# Sheet5.net
KiCad netlist of a schematic drawn in Altium Designer
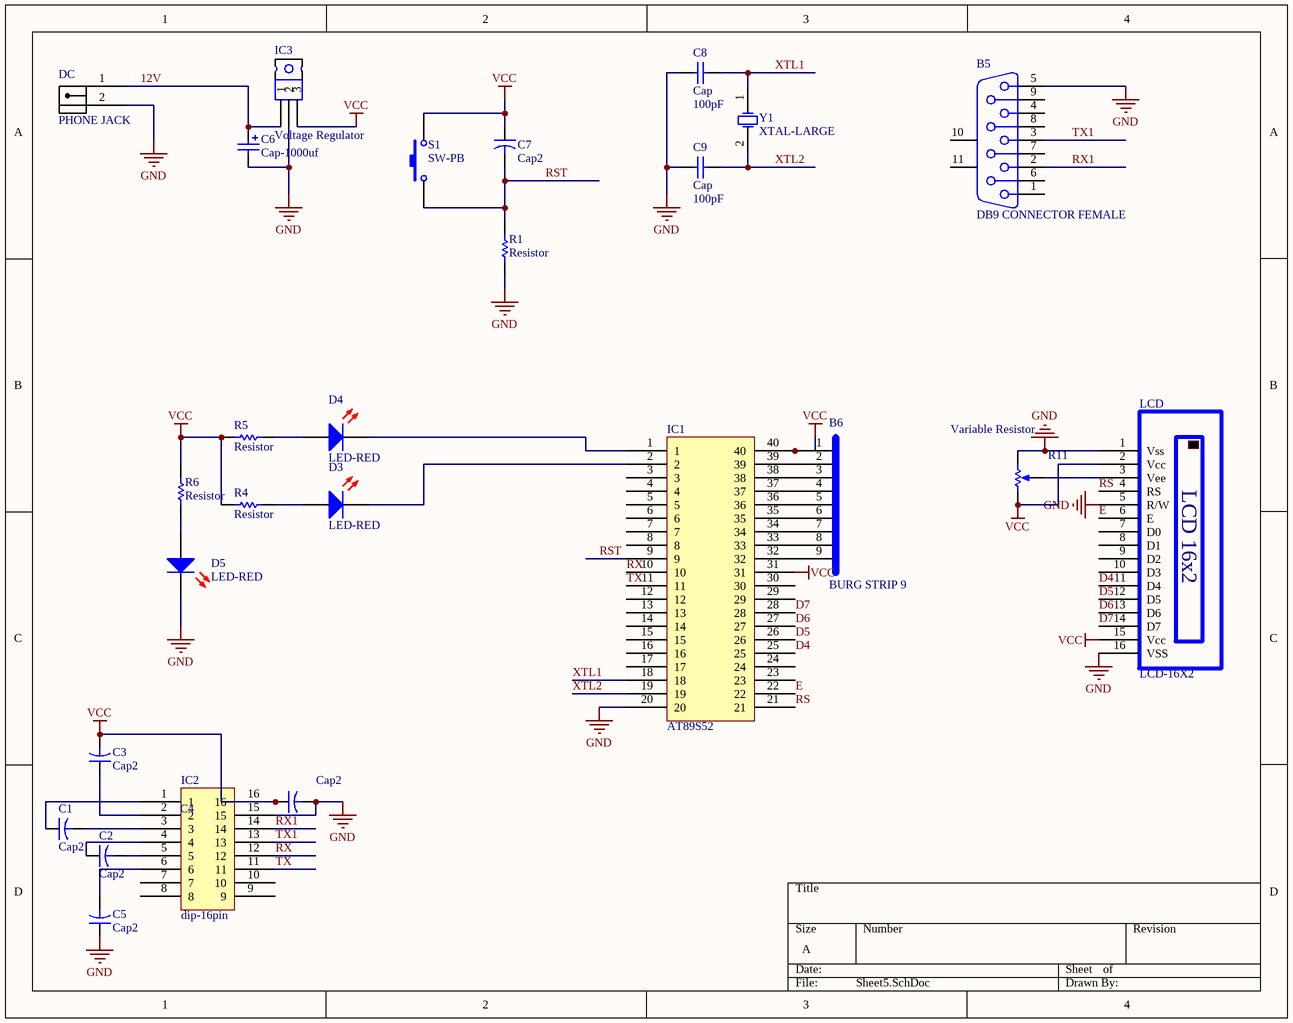
[diagram p0: Sheet5.SchDoc]

(export (version "E")
  (design (tool "Eeschema 10.0.6"))
  (components
    (comp (ref "B5")
      (value "DB9 CONNECTOR FEMALE")
      (footprint "DB9 CONNECTOR FEMALE")
      (libsource (lib "Devindia_v4.0") (part "DB9 CONNECTOR FEMALE"))
    )
    (comp (ref "B6")
      (value "BURG STRIP 9")
      (footprint "bergstrip-9pin")
      (libsource (lib "Devindia_v4.0") (part "BURG STRIP 9"))
    )
    (comp (ref "C1") (value "Cap2") (footprint "CAP-100uf") (libsource (lib "Devindia_v4.0") (part "Cap2")))
    (comp (ref "C2") (value "Cap2") (footprint "CAP-100uf") (libsource (lib "Devindia_v4.0") (part "Cap2")))
    (comp (ref "C3") (value "Cap2") (footprint "CAP-100uf") (libsource (lib "Devindia_v4.0") (part "Cap2")))
    (comp (ref "C4") (value "Cap2") (footprint "CAP-100uf") (libsource (lib "Devindia_v4.0") (part "Cap2")))
    (comp (ref "C5") (value "Cap2") (footprint "CAP-100uf") (libsource (lib "Devindia_v4.0") (part "Cap2")))
    (comp (ref "C6")
      (value "Cap-1000uf")
      (footprint "CAP-1000uf")
      (libsource (lib "Devindia_v4.0") (part "Cap-1000uf"))
    )
    (comp (ref "C7") (value "Cap2") (footprint "CAP-100uf") (libsource (lib "Devindia_v4.0") (part "Cap2")))
    (comp (ref "C8")
      (value "Cap")
      (footprint "CAP")
      (description "Capacitor")
      (fields (field (name "ALTIUM_VALUE") "100pF") (field (name "PUBLISHER") "Altium Limited"))
      (libsource (lib "Devindia_v4.0") (part "Cap"))
    )
    (comp (ref "C9")
      (value "Cap")
      (footprint "CAP")
      (description "Capacitor")
      (fields (field (name "ALTIUM_VALUE") "100pF") (field (name "PUBLISHER") "Altium Limited"))
      (libsource (lib "Devindia_v4.0") (part "Cap"))
    )
    (comp (ref "D3")
      (value "LED-RED")
      (footprint "LED-RED")
      (description "Typical BLUE SiC LED")
      (fields (field (name "PUBLISHER") "Altium Limited"))
      (libsource (lib "Devindia_v4.0") (part "LED-RED"))
    )
    (comp (ref "D4")
      (value "LED-RED")
      (footprint "LED-RED")
      (description "Typical BLUE SiC LED")
      (fields (field (name "PUBLISHER") "Altium Limited"))
      (libsource (lib "Devindia_v4.0") (part "LED-RED"))
    )
    (comp (ref "D5")
      (value "LED-RED")
      (footprint "LED-RED")
      (description "Typical BLUE SiC LED")
      (fields (field (name "PUBLISHER") "Altium Limited"))
      (libsource (lib "Devindia_v4.0") (part "LED-RED"))
    )
    (comp (ref "DC")
      (value "PHONE JACK")
      (footprint "PHONE JACK")
      (libsource (lib "Devindia_v4.0") (part "PHONE JACK"))
    )
    (comp (ref "IC1")
      (value "AT89S52")
      (footprint "AT89S52")
      (libsource (lib "Devindia_v4.0") (part "AT89S52"))
    )
    (comp (ref "IC2")
      (value "dip-16pin")
      (footprint "dip-16pin")
      (libsource (lib "Devindia_v4.0") (part "dip-16pin"))
    )
    (comp (ref "IC3")
      (value "Voltage Regulator")
      (footprint "7805 WITH HEAT-SINK")
      (libsource (lib "Devindia_v4.0") (part "7805 HEATSINK"))
    )
    (comp (ref "LCD")
      (value "LCD-16X2")
      (footprint "LCD-16x2")
      (libsource (lib "Devindia_v4.0") (part "LCD-16X2"))
    )
    (comp (ref "R1")
      (value "Resistor")
      (footprint "res-2.54x4")
      (libsource (lib "Devindia_v4.0") (part "Resistor 2.54x4"))
    )
    (comp (ref "R4")
      (value "Resistor")
      (footprint "res-2.54x4")
      (libsource (lib "Devindia_v4.0") (part "Resistor 2.54x4"))
    )
    (comp (ref "R5")
      (value "Resistor")
      (footprint "res-2.54x4")
      (libsource (lib "Devindia_v4.0") (part "Resistor 2.54x4"))
    )
    (comp (ref "R6")
      (value "Resistor")
      (footprint "res-2.54x4")
      (libsource (lib "Devindia_v4.0") (part "Resistor 2.54x4"))
    )
    (comp (ref "R11")
      (value "Variable Resistor")
      (footprint "reg-variable")
      (libsource (lib "Devindia_v4.0") (part "Variable Resistor"))
    )
    (comp (ref "S1")
      (value "SW-PB")
      (footprint "sw-pb")
      (description "Switch")
      (fields (field (name "PUBLISHER") "Altium Limited"))
      (libsource (lib "Devindia_v4.0") (part "SW-PB"))
    )
    (comp (ref "Y1")
      (value "XTAL-LARGE")
      (footprint "XTAL-LARGE")
      (description "Crystal Oscillator")
      (fields (field (name "PUBLISHER") "Altium Limited"))
      (libsource (lib "Devindia_v4.0") (part "XTAL-LARGE"))
    )
  )
  (nets
    (net (code "1") (name "/12V") (class "Default")
      (node (ref "C6") (pin "1") (pinfunction "1_1") (pintype "passive"))
      (node (ref "DC") (pin "1") (pinfunction "1_1") (pintype "passive"))
      (node (ref "IC3") (pin "1") (pinfunction "1_1") (pintype "passive"))
    )
    (net (code "2") (name "/D4") (class "Default")
      (node (ref "IC1") (pin "25") (pinfunction "25_25") (pintype "passive"))
      (node (ref "LCD") (pin "11") (pinfunction "D4_11") (pintype "passive"))
    )
    (net (code "3") (name "/D5") (class "Default")
      (node (ref "IC1") (pin "26") (pinfunction "26_26") (pintype "passive"))
      (node (ref "LCD") (pin "12") (pinfunction "D5_12") (pintype "passive"))
    )
    (net (code "4") (name "/D6") (class "Default")
      (node (ref "IC1") (pin "27") (pinfunction "27_27") (pintype "passive"))
      (node (ref "LCD") (pin "13") (pinfunction "D6_13") (pintype "passive"))
    )
    (net (code "5") (name "/D7") (class "Default")
      (node (ref "IC1") (pin "28") (pinfunction "28_28") (pintype "passive"))
      (node (ref "LCD") (pin "14") (pinfunction "D7_14") (pintype "passive"))
    )
    (net (code "6") (name "/E") (class "Default")
      (node (ref "IC1") (pin "22") (pinfunction "22_22") (pintype "passive"))
      (node (ref "LCD") (pin "6") (pinfunction "E_6") (pintype "passive"))
    )
    (net (code "7") (name "/RS") (class "Default")
      (node (ref "IC1") (pin "21") (pinfunction "21_21") (pintype "passive"))
      (node (ref "LCD") (pin "4") (pinfunction "RS_4") (pintype "passive"))
    )
    (net (code "8") (name "/RST") (class "Default")
      (node (ref "C7") (pin "2") (pinfunction "2_2") (pintype "passive"))
      (node (ref "IC1") (pin "9") (pinfunction "9_9") (pintype "passive"))
      (node (ref "R1") (pin "2") (pinfunction "2_2") (pintype "passive"))
      (node (ref "S1") (pin "1") (pinfunction "1_1") (pintype "passive"))
    )
    (net (code "9") (name "/RX") (class "Default")
      (node (ref "IC1") (pin "10") (pinfunction "10_10") (pintype "passive"))
      (node (ref "IC2") (pin "12") (pinfunction "12_12") (pintype "passive"))
    )
    (net (code "10") (name "/RX1") (class "Default")
      (node (ref "B5") (pin "2") (pinfunction "2_2") (pintype "passive"))
      (node (ref "IC2") (pin "14") (pinfunction "14_14") (pintype "passive"))
    )
    (net (code "11") (name "/TX") (class "Default")
      (node (ref "IC1") (pin "11") (pinfunction "11_11") (pintype "passive"))
      (node (ref "IC2") (pin "11") (pinfunction "11_11") (pintype "passive"))
    )
    (net (code "12") (name "/TX1") (class "Default")
      (node (ref "B5") (pin "3") (pinfunction "3_3") (pintype "passive"))
      (node (ref "IC2") (pin "13") (pinfunction "13_13") (pintype "passive"))
    )
    (net (code "13") (name "/XTL1") (class "Default")
      (node (ref "C8") (pin "2") (pinfunction "2_2") (pintype "passive"))
      (node (ref "IC1") (pin "18") (pinfunction "18_18") (pintype "passive"))
      (node (ref "Y1") (pin "1") (pinfunction "OSC1_1") (pintype "passive"))
    )
    (net (code "14") (name "/XTL2") (class "Default")
      (node (ref "C9") (pin "2") (pinfunction "2_2") (pintype "passive"))
      (node (ref "IC1") (pin "19") (pinfunction "19_19") (pintype "passive"))
      (node (ref "Y1") (pin "2") (pinfunction "OSC2_2") (pintype "passive"))
    )
    (net (code "15") (name "GND") (class "Default")
      (node (ref "B5") (pin "5") (pinfunction "5_5") (pintype "passive"))
      (node (ref "C4") (pin "2") (pinfunction "2_2") (pintype "passive"))
      (node (ref "C5") (pin "1") (pinfunction "1_1") (pintype "passive"))
      (node (ref "C6") (pin "2") (pinfunction "2_2") (pintype "passive"))
      (node (ref "C8") (pin "1") (pinfunction "1_1") (pintype "passive"))
      (node (ref "C9") (pin "1") (pinfunction "1_1") (pintype "passive"))
      (node (ref "D5") (pin "2") (pinfunction "K_2") (pintype "passive"))
      (node (ref "DC") (pin "2") (pinfunction "2_2") (pintype "passive"))
      (node (ref "IC1") (pin "20") (pinfunction "20_20") (pintype "passive"))
      (node (ref "IC2") (pin "15") (pinfunction "15_15") (pintype "passive"))
      (node (ref "IC3") (pin "2") (pinfunction "2_2") (pintype "passive"))
      (node (ref "LCD") (pin "1") (pinfunction "Vss_1") (pintype "passive"))
      (node (ref "LCD") (pin "16") (pinfunction "VSS_16") (pintype "passive"))
      (node (ref "LCD") (pin "5") (pinfunction "R/W_5") (pintype "passive"))
      (node (ref "R1") (pin "1") (pinfunction "1_1") (pintype "passive"))
      (node (ref "R11") (pin "3") (pinfunction "BOT_3") (pintype "passive"))
    )
    (net (code "16") (name "Net-(B6-Pad2)") (class "Default")
      (node (ref "B6") (pin "2") (pinfunction "2_2") (pintype "passive"))
      (node (ref "IC1") (pin "39") (pinfunction "39_39") (pintype "passive"))
    )
    (net (code "17") (name "Net-(B6-Pad3)") (class "Default")
      (node (ref "B6") (pin "3") (pinfunction "3_3") (pintype "passive"))
      (node (ref "IC1") (pin "38") (pinfunction "38_38") (pintype "passive"))
    )
    (net (code "18") (name "Net-(B6-Pad4)") (class "Default")
      (node (ref "B6") (pin "4") (pinfunction "4_4") (pintype "passive"))
      (node (ref "IC1") (pin "37") (pinfunction "37_37") (pintype "passive"))
    )
    (net (code "19") (name "Net-(B6-Pad5)") (class "Default")
      (node (ref "B6") (pin "5") (pinfunction "5_5") (pintype "passive"))
      (node (ref "IC1") (pin "36") (pinfunction "36_36") (pintype "passive"))
    )
    (net (code "20") (name "Net-(B6-Pad6)") (class "Default")
      (node (ref "B6") (pin "6") (pinfunction "6_6") (pintype "passive"))
      (node (ref "IC1") (pin "35") (pinfunction "35_35") (pintype "passive"))
    )
    (net (code "21") (name "Net-(B6-Pad7)") (class "Default")
      (node (ref "B6") (pin "7") (pinfunction "7_7") (pintype "passive"))
      (node (ref "IC1") (pin "34") (pinfunction "34_34") (pintype "passive"))
    )
    (net (code "22") (name "Net-(B6-Pad8)") (class "Default")
      (node (ref "B6") (pin "8") (pinfunction "8_8") (pintype "passive"))
      (node (ref "IC1") (pin "33") (pinfunction "33_33") (pintype "passive"))
    )
    (net (code "23") (name "Net-(B6-Pad9)") (class "Default")
      (node (ref "B6") (pin "9") (pinfunction "9_9") (pintype "passive"))
      (node (ref "IC1") (pin "32") (pinfunction "32_32") (pintype "passive"))
    )
    (net (code "24") (name "Net-(C1-Pad1)") (class "Default")
      (node (ref "C1") (pin "1") (pinfunction "1_1") (pintype "passive"))
      (node (ref "IC2") (pin "1") (pinfunction "1_1") (pintype "passive"))
    )
    (net (code "25") (name "Net-(C1-Pad2)") (class "Default")
      (node (ref "C1") (pin "2") (pinfunction "2_2") (pintype "passive"))
      (node (ref "IC2") (pin "3") (pinfunction "3_3") (pintype "passive"))
    )
    (net (code "26") (name "Net-(C2-Pad1)") (class "Default")
      (node (ref "C2") (pin "1") (pinfunction "1_1") (pintype "passive"))
      (node (ref "IC2") (pin "4") (pinfunction "4_4") (pintype "passive"))
    )
    (net (code "27") (name "Net-(C2-Pad2)") (class "Default")
      (node (ref "C2") (pin "2") (pinfunction "2_2") (pintype "passive"))
      (node (ref "IC2") (pin "5") (pinfunction "5_5") (pintype "passive"))
    )
    (net (code "28") (name "Net-(C3-Pad1)") (class "Default")
      (node (ref "C3") (pin "1") (pinfunction "1_1") (pintype "passive"))
      (node (ref "IC2") (pin "2") (pinfunction "2_2") (pintype "passive"))
    )
    (net (code "29") (name "Net-(C5-Pad2)") (class "Default")
      (node (ref "C5") (pin "2") (pinfunction "2_2") (pintype "passive"))
      (node (ref "IC2") (pin "6") (pinfunction "6_6") (pintype "passive"))
    )
    (net (code "30") (name "Net-(D3-A)") (class "Default")
      (node (ref "D3") (pin "1") (pinfunction "A_1") (pintype "passive"))
      (node (ref "R4") (pin "2") (pinfunction "2_2") (pintype "passive"))
    )
    (net (code "31") (name "Net-(D3-K)") (class "Default")
      (node (ref "D3") (pin "2") (pinfunction "K_2") (pintype "passive"))
      (node (ref "IC1") (pin "2") (pinfunction "2_2") (pintype "passive"))
    )
    (net (code "32") (name "Net-(D4-A)") (class "Default")
      (node (ref "D4") (pin "1") (pinfunction "A_1") (pintype "passive"))
      (node (ref "R5") (pin "2") (pinfunction "2_2") (pintype "passive"))
    )
    (net (code "33") (name "Net-(D4-K)") (class "Default")
      (node (ref "D4") (pin "2") (pinfunction "K_2") (pintype "passive"))
      (node (ref "IC1") (pin "1") (pinfunction "1_1") (pintype "passive"))
    )
    (net (code "34") (name "Net-(D5-A)") (class "Default")
      (node (ref "D5") (pin "1") (pinfunction "A_1") (pintype "passive"))
      (node (ref "R6") (pin "1") (pinfunction "1_1") (pintype "passive"))
    )
    (net (code "35") (name "Net-(LCD-Vee)") (class "Default")
      (node (ref "LCD") (pin "3") (pinfunction "Vee_3") (pintype "passive"))
      (node (ref "R11") (pin "2") (pinfunction "TAP_2") (pintype "passive"))
    )
    (net (code "36") (name "VCC") (class "Default")
      (node (ref "B6") (pin "1") (pinfunction "1_1") (pintype "passive"))
      (node (ref "C3") (pin "2") (pinfunction "2_2") (pintype "passive"))
      (node (ref "C4") (pin "1") (pinfunction "1_1") (pintype "passive"))
      (node (ref "C7") (pin "1") (pinfunction "1_1") (pintype "passive"))
      (node (ref "IC1") (pin "31") (pinfunction "31_31") (pintype "passive"))
      (node (ref "IC1") (pin "40") (pinfunction "40_40") (pintype "passive"))
      (node (ref "IC2") (pin "16") (pinfunction "16_16") (pintype "passive"))
      (node (ref "IC3") (pin "3") (pinfunction "3_3") (pintype "passive"))
      (node (ref "LCD") (pin "15") (pinfunction "Vcc_15") (pintype "passive"))
      (node (ref "LCD") (pin "2") (pinfunction "Vcc_2") (pintype "passive"))
      (node (ref "R11") (pin "1") (pinfunction "TOP_1") (pintype "passive"))
      (node (ref "R4") (pin "1") (pinfunction "1_1") (pintype "passive"))
      (node (ref "R5") (pin "1") (pinfunction "1_1") (pintype "passive"))
      (node (ref "R6") (pin "2") (pinfunction "2_2") (pintype "passive"))
      (node (ref "S1") (pin "2") (pinfunction "2_2") (pintype "passive"))
    )
    (net (code "37") (name "unconnected-(B5-MH1-Pad10)") (class "Default")
      (node (ref "B5") (pin "10") (pinfunction "MH1_10") (pintype "passive"))
    )
    (net (code "38") (name "unconnected-(B5-MH2-Pad11)") (class "Default")
      (node (ref "B5") (pin "11") (pinfunction "MH2_11") (pintype "passive"))
    )
    (net (code "39") (name "unconnected-(B5-Pad1)") (class "Default")
      (node (ref "B5") (pin "1") (pinfunction "1_1") (pintype "passive"))
    )
    (net (code "40") (name "unconnected-(B5-Pad4)") (class "Default")
      (node (ref "B5") (pin "4") (pinfunction "4_4") (pintype "passive"))
    )
    (net (code "41") (name "unconnected-(B5-Pad6)") (class "Default")
      (node (ref "B5") (pin "6") (pinfunction "6_6") (pintype "passive"))
    )
    (net (code "42") (name "unconnected-(B5-Pad7)") (class "Default")
      (node (ref "B5") (pin "7") (pinfunction "7_7") (pintype "passive"))
    )
    (net (code "43") (name "unconnected-(B5-Pad8)") (class "Default")
      (node (ref "B5") (pin "8") (pinfunction "8_8") (pintype "passive"))
    )
    (net (code "44") (name "unconnected-(B5-Pad9)") (class "Default")
      (node (ref "B5") (pin "9") (pinfunction "9_9") (pintype "passive"))
    )
    (net (code "45") (name "unconnected-(IC1-Pad3)") (class "Default")
      (node (ref "IC1") (pin "3") (pinfunction "3_3") (pintype "passive"))
    )
    (net (code "46") (name "unconnected-(IC1-Pad4)") (class "Default")
      (node (ref "IC1") (pin "4") (pinfunction "4_4") (pintype "passive"))
    )
    (net (code "47") (name "unconnected-(IC1-Pad5)") (class "Default")
      (node (ref "IC1") (pin "5") (pinfunction "5_5") (pintype "passive"))
    )
    (net (code "48") (name "unconnected-(IC1-Pad6)") (class "Default")
      (node (ref "IC1") (pin "6") (pinfunction "6_6") (pintype "passive"))
    )
    (net (code "49") (name "unconnected-(IC1-Pad7)") (class "Default")
      (node (ref "IC1") (pin "7") (pinfunction "7_7") (pintype "passive"))
    )
    (net (code "50") (name "unconnected-(IC1-Pad8)") (class "Default")
      (node (ref "IC1") (pin "8") (pinfunction "8_8") (pintype "passive"))
    )
    (net (code "51") (name "unconnected-(IC1-Pad12)") (class "Default")
      (node (ref "IC1") (pin "12") (pinfunction "12_12") (pintype "passive"))
    )
    (net (code "52") (name "unconnected-(IC1-Pad13)") (class "Default")
      (node (ref "IC1") (pin "13") (pinfunction "13_13") (pintype "passive"))
    )
    (net (code "53") (name "unconnected-(IC1-Pad14)") (class "Default")
      (node (ref "IC1") (pin "14") (pinfunction "14_14") (pintype "passive"))
    )
    (net (code "54") (name "unconnected-(IC1-Pad15)") (class "Default")
      (node (ref "IC1") (pin "15") (pinfunction "15_15") (pintype "passive"))
    )
    (net (code "55") (name "unconnected-(IC1-Pad16)") (class "Default")
      (node (ref "IC1") (pin "16") (pinfunction "16_16") (pintype "passive"))
    )
    (net (code "56") (name "unconnected-(IC1-Pad17)") (class "Default")
      (node (ref "IC1") (pin "17") (pinfunction "17_17") (pintype "passive"))
    )
    (net (code "57") (name "unconnected-(IC1-Pad23)") (class "Default")
      (node (ref "IC1") (pin "23") (pinfunction "23_23") (pintype "passive"))
    )
    (net (code "58") (name "unconnected-(IC1-Pad24)") (class "Default")
      (node (ref "IC1") (pin "24") (pinfunction "24_24") (pintype "passive"))
    )
    (net (code "59") (name "unconnected-(IC1-Pad29)") (class "Default")
      (node (ref "IC1") (pin "29") (pinfunction "29_29") (pintype "passive"))
    )
    (net (code "60") (name "unconnected-(IC1-Pad30)") (class "Default")
      (node (ref "IC1") (pin "30") (pinfunction "30_30") (pintype "passive"))
    )
    (net (code "61") (name "unconnected-(IC2-Pad7)") (class "Default")
      (node (ref "IC2") (pin "7") (pinfunction "7_7") (pintype "passive"))
    )
    (net (code "62") (name "unconnected-(IC2-Pad8)") (class "Default")
      (node (ref "IC2") (pin "8") (pinfunction "8_8") (pintype "passive"))
    )
    (net (code "63") (name "unconnected-(IC2-Pad9)") (class "Default")
      (node (ref "IC2") (pin "9") (pinfunction "9_9") (pintype "passive"))
    )
    (net (code "64") (name "unconnected-(IC2-Pad10)") (class "Default")
      (node (ref "IC2") (pin "10") (pinfunction "10_10") (pintype "passive"))
    )
    (net (code "65") (name "unconnected-(LCD-D0-Pad7)") (class "Default")
      (node (ref "LCD") (pin "7") (pinfunction "D0_7") (pintype "passive"))
    )
    (net (code "66") (name "unconnected-(LCD-D1-Pad8)") (class "Default")
      (node (ref "LCD") (pin "8") (pinfunction "D1_8") (pintype "passive"))
    )
    (net (code "67") (name "unconnected-(LCD-D2-Pad9)") (class "Default")
      (node (ref "LCD") (pin "9") (pinfunction "D2_9") (pintype "passive"))
    )
    (net (code "68") (name "unconnected-(LCD-D3-Pad10)") (class "Default")
      (node (ref "LCD") (pin "10") (pinfunction "D3_10") (pintype "passive"))
    )
  )
)
